# Steppers.net
KiCad netlist of a schematic drawn in Altium Designer
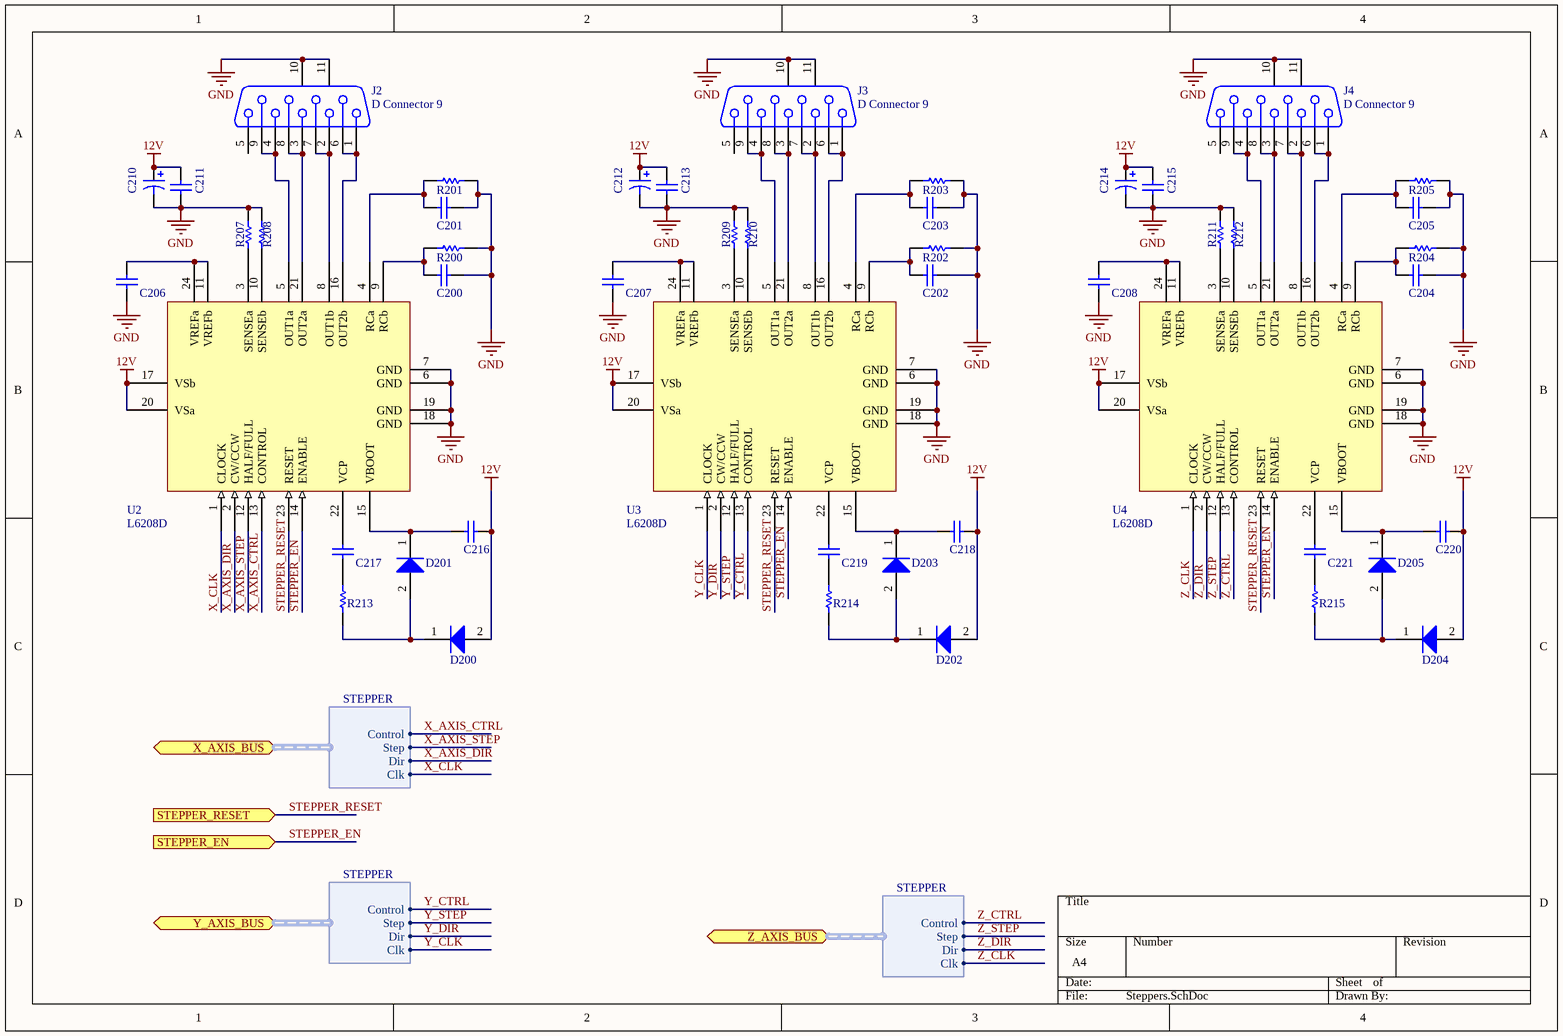
[diagram p0: Steppers.SchDoc]

(export (version "E")
  (design (tool "Eeschema 10.0.6"))
  (components
    (comp (ref "C200")
      (value "CAP 100nF 10V 1206(3216)")
      (footprint "CAPC1206(3216)190_M")
      (description "CAP 100nF 10V ±5% 1206 (3216 Metric) Thickness 1.9mm SMD")
      (fields (field (name "TOLERANCE") "Â±5%"))
      (libsource (lib "Altium Content Vault") (part "CAP"))
    )
    (comp (ref "C201")
      (value "CAP 100nF 10V 1206(3216)")
      (footprint "CAPC1206(3216)190_M")
      (description "CAP 100nF 10V ±5% 1206 (3216 Metric) Thickness 1.9mm SMD")
      (fields (field (name "TOLERANCE") "Â±5%"))
      (libsource (lib "Altium Content Vault") (part "CAP"))
    )
    (comp (ref "C202")
      (value "CAP 100nF 10V 1206(3216)")
      (footprint "CAPC1206(3216)190_M")
      (description "CAP 100nF 10V ±5% 1206 (3216 Metric) Thickness 1.9mm SMD")
      (fields (field (name "TOLERANCE") "Â±5%"))
      (libsource (lib "Altium Content Vault") (part "CAP"))
    )
    (comp (ref "C203")
      (value "CAP 100nF 10V 1206(3216)")
      (footprint "CAPC1206(3216)190_M")
      (description "CAP 100nF 10V ±5% 1206 (3216 Metric) Thickness 1.9mm SMD")
      (fields (field (name "TOLERANCE") "Â±5%"))
      (libsource (lib "Altium Content Vault") (part "CAP"))
    )
    (comp (ref "C204")
      (value "CAP 100nF 10V 1206(3216)")
      (footprint "CAPC1206(3216)190_M")
      (description "CAP 100nF 10V ±5% 1206 (3216 Metric) Thickness 1.9mm SMD")
      (fields (field (name "TOLERANCE") "Â±5%"))
      (libsource (lib "Altium Content Vault") (part "CAP"))
    )
    (comp (ref "C205")
      (value "CAP 100nF 10V 1206(3216)")
      (footprint "CAPC1206(3216)190_M")
      (description "CAP 100nF 10V ±5% 1206 (3216 Metric) Thickness 1.9mm SMD")
      (fields (field (name "TOLERANCE") "Â±5%"))
      (libsource (lib "Altium Content Vault") (part "CAP"))
    )
    (comp (ref "C206")
      (value "CAP 100nF 10V 1206(3216)")
      (footprint "CAPC1206(3216)190_M")
      (description "CAP 100nF 10V ±5% 1206 (3216 Metric) Thickness 1.9mm SMD")
      (fields (field (name "TOLERANCE") "Â±5%"))
      (libsource (lib "Altium Content Vault") (part "CAP"))
    )
    (comp (ref "C207")
      (value "CAP 100nF 10V 1206(3216)")
      (footprint "CAPC1206(3216)190_M")
      (description "CAP 100nF 10V ±5% 1206 (3216 Metric) Thickness 1.9mm SMD")
      (fields (field (name "TOLERANCE") "Â±5%"))
      (libsource (lib "Altium Content Vault") (part "CAP"))
    )
    (comp (ref "C208")
      (value "CAP 100nF 10V 1206(3216)")
      (footprint "CAPC1206(3216)190_M")
      (description "CAP 100nF 10V ±5% 1206 (3216 Metric) Thickness 1.9mm SMD")
      (fields (field (name "TOLERANCE") "Â±5%"))
      (libsource (lib "Altium Content Vault") (part "CAP"))
    )
    (comp (ref "C210")
      (value "T491B")
      (footprint "B")
      (description "Solid Tantalum Chip Capacitor, Standard T491 Series - Industrial Grade")
      (fields (field (name "PUBLISHER") "Altium Limited"))
      (libsource (lib "KEMET Chip Capacitor") (part "T491B"))
    )
    (comp (ref "C211")
      (value "CAP 100nF 10V 1206(3216)")
      (footprint "CAPC1206(3216)190_M")
      (description "CAP 100nF 10V ±5% 1206 (3216 Metric) Thickness 1.9mm SMD")
      (fields (field (name "TOLERANCE") "Â±5%"))
      (libsource (lib "Altium Content Vault") (part "CAP"))
    )
    (comp (ref "C212")
      (value "T491B")
      (footprint "B")
      (description "Solid Tantalum Chip Capacitor, Standard T491 Series - Industrial Grade")
      (fields (field (name "PUBLISHER") "Altium Limited"))
      (libsource (lib "KEMET Chip Capacitor") (part "T491B"))
    )
    (comp (ref "C213")
      (value "CAP 100nF 10V 1206(3216)")
      (footprint "CAPC1206(3216)190_M")
      (description "CAP 100nF 10V ±5% 1206 (3216 Metric) Thickness 1.9mm SMD")
      (fields (field (name "TOLERANCE") "Â±5%"))
      (libsource (lib "Altium Content Vault") (part "CAP"))
    )
    (comp (ref "C214")
      (value "T491B")
      (footprint "B")
      (description "Solid Tantalum Chip Capacitor, Standard T491 Series - Industrial Grade")
      (fields (field (name "PUBLISHER") "Altium Limited"))
      (libsource (lib "KEMET Chip Capacitor") (part "T491B"))
    )
    (comp (ref "C215")
      (value "CAP 100nF 10V 1206(3216)")
      (footprint "CAPC1206(3216)190_M")
      (description "CAP 100nF 10V ±5% 1206 (3216 Metric) Thickness 1.9mm SMD")
      (fields (field (name "TOLERANCE") "Â±5%"))
      (libsource (lib "Altium Content Vault") (part "CAP"))
    )
    (comp (ref "C216")
      (value "CAP 100nF 10V 1206(3216)")
      (footprint "CAPC1206(3216)190_M")
      (description "CAP 100nF 10V ±5% 1206 (3216 Metric) Thickness 1.9mm SMD")
      (fields (field (name "TOLERANCE") "Â±5%"))
      (libsource (lib "Altium Content Vault") (part "CAP"))
    )
    (comp (ref "C217")
      (value "CAP 100nF 10V 1206(3216)")
      (footprint "CAPC1206(3216)190_M")
      (description "CAP 100nF 10V ±5% 1206 (3216 Metric) Thickness 1.9mm SMD")
      (fields (field (name "TOLERANCE") "Â±5%"))
      (libsource (lib "Altium Content Vault") (part "CAP"))
    )
    (comp (ref "C218")
      (value "CAP 100nF 10V 1206(3216)")
      (footprint "CAPC1206(3216)190_M")
      (description "CAP 100nF 10V ±5% 1206 (3216 Metric) Thickness 1.9mm SMD")
      (fields (field (name "TOLERANCE") "Â±5%"))
      (libsource (lib "Altium Content Vault") (part "CAP"))
    )
    (comp (ref "C219")
      (value "CAP 100nF 10V 1206(3216)")
      (footprint "CAPC1206(3216)190_M")
      (description "CAP 100nF 10V ±5% 1206 (3216 Metric) Thickness 1.9mm SMD")
      (fields (field (name "TOLERANCE") "Â±5%"))
      (libsource (lib "Altium Content Vault") (part "CAP"))
    )
    (comp (ref "C220")
      (value "CAP 100nF 10V 1206(3216)")
      (footprint "CAPC1206(3216)190_M")
      (description "CAP 100nF 10V ±5% 1206 (3216 Metric) Thickness 1.9mm SMD")
      (fields (field (name "TOLERANCE") "Â±5%"))
      (libsource (lib "Altium Content Vault") (part "CAP"))
    )
    (comp (ref "C221")
      (value "CAP 100nF 10V 1206(3216)")
      (footprint "CAPC1206(3216)190_M")
      (description "CAP 100nF 10V ±5% 1206 (3216 Metric) Thickness 1.9mm SMD")
      (fields (field (name "TOLERANCE") "Â±5%"))
      (libsource (lib "Altium Content Vault") (part "CAP"))
    )
    (comp (ref "D200")
      (value "NSR0340HT1G")
      (footprint "ONSC-SOD-323-2-477-02_V")
      (description "Schottky Barrier Diode, 2-Pin SOD-323, Pb-Free, Tape and Reel")
      (fields (field (name "MANUFACTURER") "On Semiconductor"))
      (libsource (lib "Altium Content Vault") (part "CMP-1055-00472-1"))
    )
    (comp (ref "D201")
      (value "NSR0340HT1G")
      (footprint "ONSC-SOD-323-2-477-02_V")
      (description "Schottky Barrier Diode, 2-Pin SOD-323, Pb-Free, Tape and Reel")
      (fields (field (name "MANUFACTURER") "On Semiconductor"))
      (libsource (lib "Altium Content Vault") (part "CMP-1055-00472-1"))
    )
    (comp (ref "D202")
      (value "NSR0340HT1G")
      (footprint "ONSC-SOD-323-2-477-02_V")
      (description "Schottky Barrier Diode, 2-Pin SOD-323, Pb-Free, Tape and Reel")
      (fields (field (name "MANUFACTURER") "On Semiconductor"))
      (libsource (lib "Altium Content Vault") (part "CMP-1055-00472-1"))
    )
    (comp (ref "D203")
      (value "NSR0340HT1G")
      (footprint "ONSC-SOD-323-2-477-02_V")
      (description "Schottky Barrier Diode, 2-Pin SOD-323, Pb-Free, Tape and Reel")
      (fields (field (name "MANUFACTURER") "On Semiconductor"))
      (libsource (lib "Altium Content Vault") (part "CMP-1055-00472-1"))
    )
    (comp (ref "D204")
      (value "NSR0340HT1G")
      (footprint "ONSC-SOD-323-2-477-02_V")
      (description "Schottky Barrier Diode, 2-Pin SOD-323, Pb-Free, Tape and Reel")
      (fields (field (name "MANUFACTURER") "On Semiconductor"))
      (libsource (lib "Altium Content Vault") (part "CMP-1055-00472-1"))
    )
    (comp (ref "D205")
      (value "NSR0340HT1G")
      (footprint "ONSC-SOD-323-2-477-02_V")
      (description "Schottky Barrier Diode, 2-Pin SOD-323, Pb-Free, Tape and Reel")
      (fields (field (name "MANUFACTURER") "On Semiconductor"))
      (libsource (lib "Altium Content Vault") (part "CMP-1055-00472-1"))
    )
    (comp (ref "J2")
      (value "D Connector 9")
      (footprint "DSUB1.385-2H9")
      (description "Receptacle Assembly, 9 Position, Right Angle")
      (fields (field (name "PUBLISHER") "Altium Limited"))
      (libsource (lib "Miscellaneous Connectors") (part "D Connector 9"))
    )
    (comp (ref "J3")
      (value "D Connector 9")
      (footprint "DSUB1.385-2H9")
      (description "Receptacle Assembly, 9 Position, Right Angle")
      (fields (field (name "PUBLISHER") "Altium Limited"))
      (libsource (lib "Miscellaneous Connectors") (part "D Connector 9"))
    )
    (comp (ref "J4")
      (value "D Connector 9")
      (footprint "DSUB1.385-2H9")
      (description "Receptacle Assembly, 9 Position, Right Angle")
      (fields (field (name "PUBLISHER") "Altium Limited"))
      (libsource (lib "Miscellaneous Connectors") (part "D Connector 9"))
    )
    (comp (ref "R200")
      (value "1K 5% 1206(3216)")
      (footprint "RESC1206(3216)_M")
      (description "1K 0.25W 5% 1206 (3216 Metric)  SMD")
      (fields (field (name "TOLERANCE") "5 %") (field (name "POWER") "0.25 W"))
      (libsource (lib "Altium Content Vault") (part "RES"))
    )
    (comp (ref "R201")
      (value "1K 5% 1206(3216)")
      (footprint "RESC1206(3216)_M")
      (description "1K 0.25W 5% 1206 (3216 Metric)  SMD")
      (fields (field (name "TOLERANCE") "5 %") (field (name "POWER") "0.25 W"))
      (libsource (lib "Altium Content Vault") (part "RES"))
    )
    (comp (ref "R202")
      (value "1K 5% 1206(3216)")
      (footprint "RESC1206(3216)_M")
      (description "1K 0.25W 5% 1206 (3216 Metric)  SMD")
      (fields (field (name "TOLERANCE") "5 %") (field (name "POWER") "0.25 W"))
      (libsource (lib "Altium Content Vault") (part "RES"))
    )
    (comp (ref "R203")
      (value "1K 5% 1206(3216)")
      (footprint "RESC1206(3216)_M")
      (description "1K 0.25W 5% 1206 (3216 Metric)  SMD")
      (fields (field (name "TOLERANCE") "5 %") (field (name "POWER") "0.25 W"))
      (libsource (lib "Altium Content Vault") (part "RES"))
    )
    (comp (ref "R204")
      (value "1K 5% 1206(3216)")
      (footprint "RESC1206(3216)_M")
      (description "1K 0.25W 5% 1206 (3216 Metric)  SMD")
      (fields (field (name "TOLERANCE") "5 %") (field (name "POWER") "0.25 W"))
      (libsource (lib "Altium Content Vault") (part "RES"))
    )
    (comp (ref "R205")
      (value "1K 5% 1206(3216)")
      (footprint "RESC1206(3216)_M")
      (description "1K 0.25W 5% 1206 (3216 Metric)  SMD")
      (fields (field (name "TOLERANCE") "5 %") (field (name "POWER") "0.25 W"))
      (libsource (lib "Altium Content Vault") (part "RES"))
    )
    (comp (ref "R207")
      (value "1R 5% 1210(3225)")
      (footprint "RESC1210(3225)_L")
      (description "1R 0.5W 5% 1210 (3225 Metric)  SMD")
      (fields (field (name "POWER") "0.5 W") (field (name "TOLERANCE") "5 %"))
      (libsource (lib "Altium Content Vault") (part "RES"))
    )
    (comp (ref "R208")
      (value "1R 5% 1210(3225)")
      (footprint "RESC1210(3225)_L")
      (description "1R 0.5W 5% 1210 (3225 Metric)  SMD")
      (fields (field (name "POWER") "0.5 W") (field (name "TOLERANCE") "5 %"))
      (libsource (lib "Altium Content Vault") (part "RES"))
    )
    (comp (ref "R209")
      (value "1R 5% 1210(3225)")
      (footprint "RESC1210(3225)_L")
      (description "1R 0.5W 5% 1210 (3225 Metric)  SMD")
      (fields (field (name "POWER") "0.5 W") (field (name "TOLERANCE") "5 %"))
      (libsource (lib "Altium Content Vault") (part "RES"))
    )
    (comp (ref "R210")
      (value "1R 5% 1210(3225)")
      (footprint "RESC1210(3225)_L")
      (description "1R 0.5W 5% 1210 (3225 Metric)  SMD")
      (fields (field (name "POWER") "0.5 W") (field (name "TOLERANCE") "5 %"))
      (libsource (lib "Altium Content Vault") (part "RES"))
    )
    (comp (ref "R211")
      (value "1R 5% 1210(3225)")
      (footprint "RESC1210(3225)_L")
      (description "1R 0.5W 5% 1210 (3225 Metric)  SMD")
      (fields (field (name "POWER") "0.5 W") (field (name "TOLERANCE") "5 %"))
      (libsource (lib "Altium Content Vault") (part "RES"))
    )
    (comp (ref "R212")
      (value "1R 5% 1210(3225)")
      (footprint "RESC1210(3225)_L")
      (description "1R 0.5W 5% 1210 (3225 Metric)  SMD")
      (fields (field (name "POWER") "0.5 W") (field (name "TOLERANCE") "5 %"))
      (libsource (lib "Altium Content Vault") (part "RES"))
    )
    (comp (ref "R213")
      (value "1K 5% 1206(3216)")
      (footprint "RESC1206(3216)_M")
      (description "1K 0.25W 5% 1206 (3216 Metric)  SMD")
      (fields (field (name "TOLERANCE") "5 %") (field (name "POWER") "0.25 W"))
      (libsource (lib "Altium Content Vault") (part "RES"))
    )
    (comp (ref "R214")
      (value "1K 5% 1206(3216)")
      (footprint "RESC1206(3216)_M")
      (description "1K 0.25W 5% 1206 (3216 Metric)  SMD")
      (fields (field (name "TOLERANCE") "5 %") (field (name "POWER") "0.25 W"))
      (libsource (lib "Altium Content Vault") (part "RES"))
    )
    (comp (ref "R215")
      (value "1K 5% 1206(3216)")
      (footprint "RESC1206(3216)_M")
      (description "1K 0.25W 5% 1206 (3216 Metric)  SMD")
      (fields (field (name "TOLERANCE") "5 %") (field (name "POWER") "0.25 W"))
      (libsource (lib "Altium Content Vault") (part "RES"))
    )
    (comp (ref "U2")
      (value "L6208D")
      (footprint "SO24_L")
      (description "Stepper controler")
      (libsource (lib "INSA") (part "L6208D"))
    )
    (comp (ref "U3")
      (value "L6208D")
      (footprint "SO24_L")
      (description "Stepper controler")
      (libsource (lib "INSA") (part "L6208D"))
    )
    (comp (ref "U4")
      (value "L6208D")
      (footprint "SO24_L")
      (description "Stepper controler")
      (libsource (lib "INSA") (part "L6208D"))
    )
  )
  (nets
    (net (code "2") (name "/STEPPER_EN") (class "Default")
      (node (ref "U2") (pin "14") (pinfunction "ENABLE_14") (pintype "input"))
      (node (ref "U3") (pin "14") (pinfunction "ENABLE_14") (pintype "input"))
      (node (ref "U4") (pin "14") (pinfunction "ENABLE_14") (pintype "input"))
    )
    (net (code "3") (name "/STEPPER_RESET") (class "Default")
      (node (ref "U2") (pin "23") (pinfunction "RESET_23") (pintype "input"))
      (node (ref "U3") (pin "23") (pinfunction "RESET_23") (pintype "input"))
      (node (ref "U4") (pin "23") (pinfunction "RESET_23") (pintype "input"))
    )
    (net (code "4") (name "/X_AXIS_CTRL") (class "Default")
      (node (ref "U2") (pin "13") (pinfunction "CONTROL_13") (pintype "input"))
    )
    (net (code "5") (name "/X_AXIS_DIR") (class "Default")
      (node (ref "U2") (pin "2") (pinfunction "CW/CCW_2") (pintype "input"))
    )
    (net (code "6") (name "/X_AXIS_STEP") (class "Default")
      (node (ref "U2") (pin "12") (pinfunction "HALF/FULL_12") (pintype "input"))
    )
    (net (code "7") (name "/X_CLK") (class "Default")
      (node (ref "U2") (pin "1") (pinfunction "CLOCK_1") (pintype "input"))
    )
    (net (code "8") (name "/Y_CLK") (class "Default")
      (node (ref "U3") (pin "1") (pinfunction "CLOCK_1") (pintype "input"))
    )
    (net (code "9") (name "/Y_CTRL") (class "Default")
      (node (ref "U3") (pin "13") (pinfunction "CONTROL_13") (pintype "input"))
    )
    (net (code "10") (name "/Y_DIR") (class "Default")
      (node (ref "U3") (pin "2") (pinfunction "CW/CCW_2") (pintype "input"))
    )
    (net (code "11") (name "/Y_STEP") (class "Default")
      (node (ref "U3") (pin "12") (pinfunction "HALF/FULL_12") (pintype "input"))
    )
    (net (code "12") (name "/Z_CLK") (class "Default")
      (node (ref "U4") (pin "1") (pinfunction "CLOCK_1") (pintype "input"))
    )
    (net (code "13") (name "/Z_CTRL") (class "Default")
      (node (ref "U4") (pin "13") (pinfunction "CONTROL_13") (pintype "input"))
    )
    (net (code "14") (name "/Z_DIR") (class "Default")
      (node (ref "U4") (pin "2") (pinfunction "CW/CCW_2") (pintype "input"))
    )
    (net (code "15") (name "/Z_STEP") (class "Default")
      (node (ref "U4") (pin "12") (pinfunction "HALF/FULL_12") (pintype "input"))
    )
    (net (code "17") (name "12V") (class "Default")
      (node (ref "C210") (pin "1") (pinfunction "1_1") (pintype "passive"))
      (node (ref "C211") (pin "2") (pinfunction "2_2") (pintype "passive"))
      (node (ref "C212") (pin "1") (pinfunction "1_1") (pintype "passive"))
      (node (ref "C213") (pin "2") (pinfunction "2_2") (pintype "passive"))
      (node (ref "C214") (pin "1") (pinfunction "1_1") (pintype "passive"))
      (node (ref "C215") (pin "2") (pinfunction "2_2") (pintype "passive"))
      (node (ref "C216") (pin "1") (pinfunction "1_1") (pintype "passive"))
      (node (ref "C218") (pin "1") (pinfunction "1_1") (pintype "passive"))
      (node (ref "C220") (pin "1") (pinfunction "1_1") (pintype "passive"))
      (node (ref "D200") (pin "2") (pinfunction "A_2") (pintype "passive"))
      (node (ref "D202") (pin "2") (pinfunction "A_2") (pintype "passive"))
      (node (ref "D204") (pin "2") (pinfunction "A_2") (pintype "passive"))
      (node (ref "U2") (pin "17") (pinfunction "VSb_17") (pintype "power_in"))
      (node (ref "U2") (pin "20") (pinfunction "VSa_20") (pintype "power_in"))
      (node (ref "U3") (pin "17") (pinfunction "VSb_17") (pintype "power_in"))
      (node (ref "U3") (pin "20") (pinfunction "VSa_20") (pintype "power_in"))
      (node (ref "U4") (pin "17") (pinfunction "VSb_17") (pintype "power_in"))
      (node (ref "U4") (pin "20") (pinfunction "VSa_20") (pintype "power_in"))
    )
    (net (code "18") (name "GND") (class "Default")
      (node (ref "C200") (pin "2") (pinfunction "2_2") (pintype "passive"))
      (node (ref "C201") (pin "2") (pinfunction "2_2") (pintype "passive"))
      (node (ref "C202") (pin "2") (pinfunction "2_2") (pintype "passive"))
      (node (ref "C203") (pin "2") (pinfunction "2_2") (pintype "passive"))
      (node (ref "C204") (pin "2") (pinfunction "2_2") (pintype "passive"))
      (node (ref "C205") (pin "2") (pinfunction "2_2") (pintype "passive"))
      (node (ref "C206") (pin "1") (pinfunction "1_1") (pintype "passive"))
      (node (ref "C207") (pin "1") (pinfunction "1_1") (pintype "passive"))
      (node (ref "C208") (pin "1") (pinfunction "1_1") (pintype "passive"))
      (node (ref "C210") (pin "2") (pinfunction "2_2") (pintype "passive"))
      (node (ref "C211") (pin "1") (pinfunction "1_1") (pintype "passive"))
      (node (ref "C212") (pin "2") (pinfunction "2_2") (pintype "passive"))
      (node (ref "C213") (pin "1") (pinfunction "1_1") (pintype "passive"))
      (node (ref "C214") (pin "2") (pinfunction "2_2") (pintype "passive"))
      (node (ref "C215") (pin "1") (pinfunction "1_1") (pintype "passive"))
      (node (ref "J2") (pin "10") (pinfunction "MH1_10") (pintype "passive"))
      (node (ref "J2") (pin "11") (pinfunction "MH2_11") (pintype "passive"))
      (node (ref "J3") (pin "10") (pinfunction "MH1_10") (pintype "passive"))
      (node (ref "J3") (pin "11") (pinfunction "MH2_11") (pintype "passive"))
      (node (ref "J4") (pin "10") (pinfunction "MH1_10") (pintype "passive"))
      (node (ref "J4") (pin "11") (pinfunction "MH2_11") (pintype "passive"))
      (node (ref "R200") (pin "2") (pinfunction "2_2") (pintype "passive"))
      (node (ref "R201") (pin "2") (pinfunction "2_2") (pintype "passive"))
      (node (ref "R202") (pin "2") (pinfunction "2_2") (pintype "passive"))
      (node (ref "R203") (pin "2") (pinfunction "2_2") (pintype "passive"))
      (node (ref "R204") (pin "2") (pinfunction "2_2") (pintype "passive"))
      (node (ref "R205") (pin "2") (pinfunction "2_2") (pintype "passive"))
      (node (ref "R207") (pin "2") (pinfunction "2_2") (pintype "passive"))
      (node (ref "R208") (pin "2") (pinfunction "2_2") (pintype "passive"))
      (node (ref "R209") (pin "2") (pinfunction "2_2") (pintype "passive"))
      (node (ref "R210") (pin "2") (pinfunction "2_2") (pintype "passive"))
      (node (ref "R211") (pin "2") (pinfunction "2_2") (pintype "passive"))
      (node (ref "R212") (pin "2") (pinfunction "2_2") (pintype "passive"))
      (node (ref "U2") (pin "18") (pinfunction "GND_18") (pintype "power_in"))
      (node (ref "U2") (pin "19") (pinfunction "GND_19") (pintype "power_in"))
      (node (ref "U2") (pin "6") (pinfunction "GND_6") (pintype "power_in"))
      (node (ref "U2") (pin "7") (pinfunction "GND_7") (pintype "power_in"))
      (node (ref "U3") (pin "18") (pinfunction "GND_18") (pintype "power_in"))
      (node (ref "U3") (pin "19") (pinfunction "GND_19") (pintype "power_in"))
      (node (ref "U3") (pin "6") (pinfunction "GND_6") (pintype "power_in"))
      (node (ref "U3") (pin "7") (pinfunction "GND_7") (pintype "power_in"))
      (node (ref "U4") (pin "18") (pinfunction "GND_18") (pintype "power_in"))
      (node (ref "U4") (pin "19") (pinfunction "GND_19") (pintype "power_in"))
      (node (ref "U4") (pin "6") (pinfunction "GND_6") (pintype "power_in"))
      (node (ref "U4") (pin "7") (pinfunction "GND_7") (pintype "power_in"))
    )
    (net (code "19") (name "Net-(C217-Pad1)") (class "Default")
      (node (ref "C217") (pin "1") (pinfunction "1_1") (pintype "passive"))
      (node (ref "R213") (pin "2") (pinfunction "2_2") (pintype "passive"))
    )
    (net (code "20") (name "Net-(C219-Pad1)") (class "Default")
      (node (ref "C219") (pin "1") (pinfunction "1_1") (pintype "passive"))
      (node (ref "R214") (pin "2") (pinfunction "2_2") (pintype "passive"))
    )
    (net (code "21") (name "Net-(C221-Pad1)") (class "Default")
      (node (ref "C221") (pin "1") (pinfunction "1_1") (pintype "passive"))
      (node (ref "R215") (pin "2") (pinfunction "2_2") (pintype "passive"))
    )
    (net (code "22") (name "Net-(D200-K)") (class "Default")
      (node (ref "D200") (pin "1") (pinfunction "K_1") (pintype "passive"))
      (node (ref "D201") (pin "2") (pinfunction "A_2") (pintype "passive"))
      (node (ref "R213") (pin "1") (pinfunction "1_1") (pintype "passive"))
    )
    (net (code "23") (name "Net-(D201-K)") (class "Default")
      (node (ref "C216") (pin "2") (pinfunction "2_2") (pintype "passive"))
      (node (ref "D201") (pin "1") (pinfunction "K_1") (pintype "passive"))
      (node (ref "U2") (pin "15") (pinfunction "VBOOT_15") (pintype "passive"))
    )
    (net (code "24") (name "Net-(D202-K)") (class "Default")
      (node (ref "D202") (pin "1") (pinfunction "K_1") (pintype "passive"))
      (node (ref "D203") (pin "2") (pinfunction "A_2") (pintype "passive"))
      (node (ref "R214") (pin "1") (pinfunction "1_1") (pintype "passive"))
    )
    (net (code "25") (name "Net-(D203-K)") (class "Default")
      (node (ref "C218") (pin "2") (pinfunction "2_2") (pintype "passive"))
      (node (ref "D203") (pin "1") (pinfunction "K_1") (pintype "passive"))
      (node (ref "U3") (pin "15") (pinfunction "VBOOT_15") (pintype "passive"))
    )
    (net (code "26") (name "Net-(D204-K)") (class "Default")
      (node (ref "D204") (pin "1") (pinfunction "K_1") (pintype "passive"))
      (node (ref "D205") (pin "2") (pinfunction "A_2") (pintype "passive"))
      (node (ref "R215") (pin "1") (pinfunction "1_1") (pintype "passive"))
    )
    (net (code "27") (name "Net-(D205-K)") (class "Default")
      (node (ref "C220") (pin "2") (pinfunction "2_2") (pintype "passive"))
      (node (ref "D205") (pin "1") (pinfunction "K_1") (pintype "passive"))
      (node (ref "U4") (pin "15") (pinfunction "VBOOT_15") (pintype "passive"))
    )
    (net (code "28") (name "Net-(U2-OUT1a)") (class "Default")
      (node (ref "J2") (pin "4") (pinfunction "4_4") (pintype "passive"))
      (node (ref "J2") (pin "9") (pinfunction "9_9") (pintype "passive"))
      (node (ref "U2") (pin "5") (pinfunction "OUT1a_5") (pintype "passive"))
    )
    (net (code "29") (name "Net-(U2-OUT1b)") (class "Default")
      (node (ref "J2") (pin "2") (pinfunction "2_2") (pintype "passive"))
      (node (ref "J2") (pin "7") (pinfunction "7_7") (pintype "passive"))
      (node (ref "U2") (pin "8") (pinfunction "OUT1b_8") (pintype "passive"))
    )
    (net (code "30") (name "Net-(U2-OUT2a)") (class "Default")
      (node (ref "J2") (pin "3") (pinfunction "3_3") (pintype "passive"))
      (node (ref "J2") (pin "8") (pinfunction "8_8") (pintype "passive"))
      (node (ref "U2") (pin "21") (pinfunction "OUT2a_21") (pintype "passive"))
    )
    (net (code "31") (name "Net-(U2-OUT2b)") (class "Default")
      (node (ref "J2") (pin "1") (pinfunction "1_1") (pintype "passive"))
      (node (ref "J2") (pin "6") (pinfunction "6_6") (pintype "passive"))
      (node (ref "U2") (pin "16") (pinfunction "OUT2b_16") (pintype "passive"))
    )
    (net (code "32") (name "Net-(U2-RCa)") (class "Default")
      (node (ref "C201") (pin "1") (pinfunction "1_1") (pintype "passive"))
      (node (ref "R201") (pin "1") (pinfunction "1_1") (pintype "passive"))
      (node (ref "U2") (pin "4") (pinfunction "RCa_4") (pintype "passive"))
    )
    (net (code "33") (name "Net-(U2-RCb)") (class "Default")
      (node (ref "C200") (pin "1") (pinfunction "1_1") (pintype "passive"))
      (node (ref "R200") (pin "1") (pinfunction "1_1") (pintype "passive"))
      (node (ref "U2") (pin "9") (pinfunction "RCb_9") (pintype "passive"))
    )
    (net (code "34") (name "Net-(U2-SENSEa)") (class "Default")
      (node (ref "R207") (pin "1") (pinfunction "1_1") (pintype "passive"))
      (node (ref "U2") (pin "3") (pinfunction "SENSEa_3") (pintype "passive"))
    )
    (net (code "35") (name "Net-(U2-SENSEb)") (class "Default")
      (node (ref "R208") (pin "1") (pinfunction "1_1") (pintype "passive"))
      (node (ref "U2") (pin "10") (pinfunction "SENSEb_10") (pintype "passive"))
    )
    (net (code "36") (name "Net-(U2-VCP)") (class "Default")
      (node (ref "C217") (pin "2") (pinfunction "2_2") (pintype "passive"))
      (node (ref "U2") (pin "22") (pinfunction "VCP_22") (pintype "passive"))
    )
    (net (code "37") (name "Net-(U2-VREFa)") (class "Default")
      (node (ref "C206") (pin "2") (pinfunction "2_2") (pintype "passive"))
      (node (ref "U2") (pin "11") (pinfunction "VREFb_11") (pintype "passive"))
      (node (ref "U2") (pin "24") (pinfunction "VREFa_24") (pintype "passive"))
    )
    (net (code "38") (name "Net-(U3-OUT1a)") (class "Default")
      (node (ref "J3") (pin "4") (pinfunction "4_4") (pintype "passive"))
      (node (ref "J3") (pin "9") (pinfunction "9_9") (pintype "passive"))
      (node (ref "U3") (pin "5") (pinfunction "OUT1a_5") (pintype "passive"))
    )
    (net (code "39") (name "Net-(U3-OUT1b)") (class "Default")
      (node (ref "J3") (pin "2") (pinfunction "2_2") (pintype "passive"))
      (node (ref "J3") (pin "7") (pinfunction "7_7") (pintype "passive"))
      (node (ref "U3") (pin "8") (pinfunction "OUT1b_8") (pintype "passive"))
    )
    (net (code "40") (name "Net-(U3-OUT2a)") (class "Default")
      (node (ref "J3") (pin "3") (pinfunction "3_3") (pintype "passive"))
      (node (ref "J3") (pin "8") (pinfunction "8_8") (pintype "passive"))
      (node (ref "U3") (pin "21") (pinfunction "OUT2a_21") (pintype "passive"))
    )
    (net (code "41") (name "Net-(U3-OUT2b)") (class "Default")
      (node (ref "J3") (pin "1") (pinfunction "1_1") (pintype "passive"))
      (node (ref "J3") (pin "6") (pinfunction "6_6") (pintype "passive"))
      (node (ref "U3") (pin "16") (pinfunction "OUT2b_16") (pintype "passive"))
    )
    (net (code "42") (name "Net-(U3-RCa)") (class "Default")
      (node (ref "C203") (pin "1") (pinfunction "1_1") (pintype "passive"))
      (node (ref "R203") (pin "1") (pinfunction "1_1") (pintype "passive"))
      (node (ref "U3") (pin "4") (pinfunction "RCa_4") (pintype "passive"))
    )
    (net (code "43") (name "Net-(U3-RCb)") (class "Default")
      (node (ref "C202") (pin "1") (pinfunction "1_1") (pintype "passive"))
      (node (ref "R202") (pin "1") (pinfunction "1_1") (pintype "passive"))
      (node (ref "U3") (pin "9") (pinfunction "RCb_9") (pintype "passive"))
    )
    (net (code "44") (name "Net-(U3-SENSEa)") (class "Default")
      (node (ref "R209") (pin "1") (pinfunction "1_1") (pintype "passive"))
      (node (ref "U3") (pin "3") (pinfunction "SENSEa_3") (pintype "passive"))
    )
    (net (code "45") (name "Net-(U3-SENSEb)") (class "Default")
      (node (ref "R210") (pin "1") (pinfunction "1_1") (pintype "passive"))
      (node (ref "U3") (pin "10") (pinfunction "SENSEb_10") (pintype "passive"))
    )
    (net (code "46") (name "Net-(U3-VCP)") (class "Default")
      (node (ref "C219") (pin "2") (pinfunction "2_2") (pintype "passive"))
      (node (ref "U3") (pin "22") (pinfunction "VCP_22") (pintype "passive"))
    )
    (net (code "47") (name "Net-(U3-VREFa)") (class "Default")
      (node (ref "C207") (pin "2") (pinfunction "2_2") (pintype "passive"))
      (node (ref "U3") (pin "11") (pinfunction "VREFb_11") (pintype "passive"))
      (node (ref "U3") (pin "24") (pinfunction "VREFa_24") (pintype "passive"))
    )
    (net (code "48") (name "Net-(U4-OUT1a)") (class "Default")
      (node (ref "J4") (pin "4") (pinfunction "4_4") (pintype "passive"))
      (node (ref "J4") (pin "9") (pinfunction "9_9") (pintype "passive"))
      (node (ref "U4") (pin "5") (pinfunction "OUT1a_5") (pintype "passive"))
    )
    (net (code "49") (name "Net-(U4-OUT1b)") (class "Default")
      (node (ref "J4") (pin "2") (pinfunction "2_2") (pintype "passive"))
      (node (ref "J4") (pin "7") (pinfunction "7_7") (pintype "passive"))
      (node (ref "U4") (pin "8") (pinfunction "OUT1b_8") (pintype "passive"))
    )
    (net (code "50") (name "Net-(U4-OUT2a)") (class "Default")
      (node (ref "J4") (pin "3") (pinfunction "3_3") (pintype "passive"))
      (node (ref "J4") (pin "8") (pinfunction "8_8") (pintype "passive"))
      (node (ref "U4") (pin "21") (pinfunction "OUT2a_21") (pintype "passive"))
    )
    (net (code "51") (name "Net-(U4-OUT2b)") (class "Default")
      (node (ref "J4") (pin "1") (pinfunction "1_1") (pintype "passive"))
      (node (ref "J4") (pin "6") (pinfunction "6_6") (pintype "passive"))
      (node (ref "U4") (pin "16") (pinfunction "OUT2b_16") (pintype "passive"))
    )
    (net (code "52") (name "Net-(U4-RCa)") (class "Default")
      (node (ref "C205") (pin "1") (pinfunction "1_1") (pintype "passive"))
      (node (ref "R205") (pin "1") (pinfunction "1_1") (pintype "passive"))
      (node (ref "U4") (pin "4") (pinfunction "RCa_4") (pintype "passive"))
    )
    (net (code "53") (name "Net-(U4-RCb)") (class "Default")
      (node (ref "C204") (pin "1") (pinfunction "1_1") (pintype "passive"))
      (node (ref "R204") (pin "1") (pinfunction "1_1") (pintype "passive"))
      (node (ref "U4") (pin "9") (pinfunction "RCb_9") (pintype "passive"))
    )
    (net (code "54") (name "Net-(U4-SENSEa)") (class "Default")
      (node (ref "R211") (pin "1") (pinfunction "1_1") (pintype "passive"))
      (node (ref "U4") (pin "3") (pinfunction "SENSEa_3") (pintype "passive"))
    )
    (net (code "55") (name "Net-(U4-SENSEb)") (class "Default")
      (node (ref "R212") (pin "1") (pinfunction "1_1") (pintype "passive"))
      (node (ref "U4") (pin "10") (pinfunction "SENSEb_10") (pintype "passive"))
    )
    (net (code "56") (name "Net-(U4-VCP)") (class "Default")
      (node (ref "C221") (pin "2") (pinfunction "2_2") (pintype "passive"))
      (node (ref "U4") (pin "22") (pinfunction "VCP_22") (pintype "passive"))
    )
    (net (code "57") (name "Net-(U4-VREFa)") (class "Default")
      (node (ref "C208") (pin "2") (pinfunction "2_2") (pintype "passive"))
      (node (ref "U4") (pin "11") (pinfunction "VREFb_11") (pintype "passive"))
      (node (ref "U4") (pin "24") (pinfunction "VREFa_24") (pintype "passive"))
    )
    (net (code "58") (name "unconnected-(J2-Pad5)") (class "Default")
      (node (ref "J2") (pin "5") (pinfunction "5_5") (pintype "passive"))
    )
    (net (code "59") (name "unconnected-(J3-Pad5)") (class "Default")
      (node (ref "J3") (pin "5") (pinfunction "5_5") (pintype "passive"))
    )
    (net (code "60") (name "unconnected-(J4-Pad5)") (class "Default")
      (node (ref "J4") (pin "5") (pinfunction "5_5") (pintype "passive"))
    )
  )
)
